# Fonte.net
KiCad netlist of a schematic drawn in Altium Designer
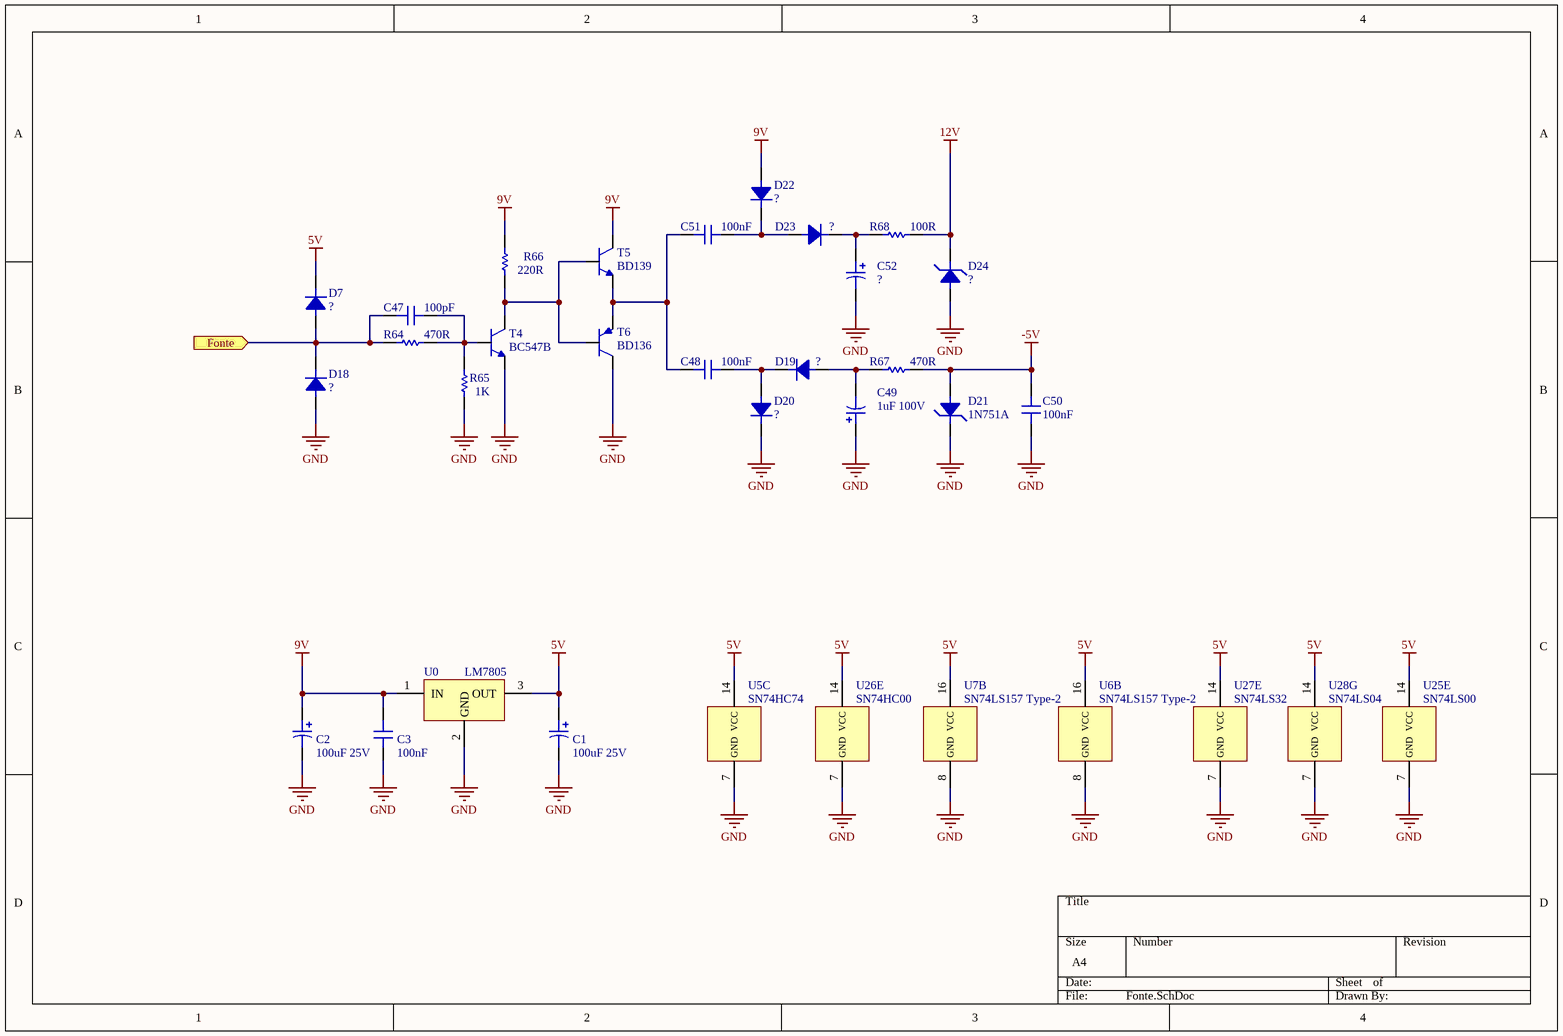
[diagram p0: Fonte.SchDoc]

(export (version "E")
  (design (tool "Eeschema 10.0.6"))
  (components
    (comp (ref "C1")
      (value "100uF 25V")
      (footprint "ECA 6.3x11.2")
      (libsource (lib "Panasonic") (part "ECA1EM101"))
    )
    (comp (ref "C2")
      (value "100uF 25V")
      (footprint "ECA 6.3x11.2")
      (libsource (lib "Panasonic") (part "ECA1EM101"))
    )
    (comp (ref "C3") (value "100nF") (footprint "DiskCapacitor") (libsource (lib "Basic") (part "Capacitor")))
    (comp (ref "C47")
      (value "100pF")
      (footprint "DiskCapacitor")
      (libsource (lib "Basic") (part "Capacitor"))
    )
    (comp (ref "C48")
      (value "100nF")
      (footprint "DiskCapacitor")
      (libsource (lib "Basic") (part "Capacitor"))
    )
    (comp (ref "C49")
      (value "1uF 100V")
      (footprint "ECA 5x11")
      (libsource (lib "Panasonic") (part "ECA2AM2R2"))
    )
    (comp (ref "C50")
      (value "100nF")
      (footprint "DiskCapacitor")
      (libsource (lib "Basic") (part "Capacitor"))
    )
    (comp (ref "C51")
      (value "100nF")
      (footprint "DiskCapacitor")
      (libsource (lib "Basic") (part "Capacitor"))
    )
    (comp (ref "C52") (value "?") (footprint "ECA 5x11") (libsource (lib "Panasonic") (part "ECA1CM100")))
    (comp (ref "D7") (value "?") (footprint "DO-15") (libsource (lib "Basic") (part "Diode")))
    (comp (ref "D18") (value "?") (footprint "DO-15") (libsource (lib "Basic") (part "Diode")))
    (comp (ref "D19") (value "?") (footprint "DO-15") (libsource (lib "Basic") (part "Diode")))
    (comp (ref "D20") (value "?") (footprint "DO-15") (libsource (lib "Basic") (part "Diode")))
    (comp (ref "D21")
      (value "1N751A")
      (footprint "DO-15")
      (description "5V1 500mW")
      (libsource (lib "Basic") (part "Diode Zener"))
    )
    (comp (ref "D22") (value "?") (footprint "DO-15") (libsource (lib "Basic") (part "Diode")))
    (comp (ref "D23") (value "?") (footprint "DO-15") (libsource (lib "Basic") (part "Diode")))
    (comp (ref "D24") (value "?") (footprint "DO-15") (libsource (lib "Basic") (part "Diode Zener")))
    (comp (ref "R64") (value "470R") (footprint "CR25") (libsource (lib "Basic") (part "Resistor")))
    (comp (ref "R65") (value "1K") (footprint "CR25") (libsource (lib "Basic") (part "Resistor")))
    (comp (ref "R66") (value "220R") (footprint "CR25") (libsource (lib "Basic") (part "Resistor")))
    (comp (ref "R67") (value "470R") (footprint "CR25") (libsource (lib "Basic") (part "Resistor")))
    (comp (ref "R68") (value "100R") (footprint "CR25") (libsource (lib "Basic") (part "Resistor")))
    (comp (ref "T4")
      (value "BC547B")
      (footprint "TO-92")
      (description "NPN Epitaxial Silicon Transistor")
      (libsource (lib "Basic") (part "BC546_47_48_49_50"))
    )
    (comp (ref "T5")
      (value "BD139")
      (footprint "TO-126")
      (description "NPN Epitaxial Silicon Transistor")
      (libsource (lib "Basic") (part "BD135_37_39"))
    )
    (comp (ref "T6")
      (value "BD136")
      (footprint "TO-126")
      (description "PNP Epitaxial Silicon Transistor")
      (libsource (lib "Basic") (part "BD136_38_40"))
    )
    (comp (ref "U0")
      (value "LM7805")
      (footprint "TO-220")
      (description "LM7805 - Positive Voltage Regulator")
      (libsource (lib "ST Microelectronics") (part "LM7805"))
    )
    (comp (ref "U5")
      (value "SN74HC74")
      (footprint "TSSOP14")
      (description "Dual D-Type Positive-Edge-Triggered Flip-Flops With Clear and Preset")
      (libsource (lib "Texas Instruments") (part "SN74HC74"))
    )
    (comp (ref "U6")
      (value "SN74LS157 Type-2")
      (footprint "TSSOP16")
      (description "Quadruple 2-Line To 1-Line Data Selectors/Mutiplexers")
      (libsource (lib "Texas Instruments") (part "SN74HC157 Type-2"))
    )
    (comp (ref "U7")
      (value "SN74LS157 Type-2")
      (footprint "TSSOP16")
      (description "Quadruple 2-Line To 1-Line Data Selectors/Mutiplexers")
      (libsource (lib "Texas Instruments") (part "SN74HC157 Type-2"))
    )
    (comp (ref "U25")
      (value "SN74LS00")
      (footprint "TSSOP14")
      (description "Quadruple 2-Input Positive-NAND Gates")
      (libsource (lib "Texas Instruments") (part "SN74HC00"))
    )
    (comp (ref "U26")
      (value "SN74HC00")
      (footprint "TSSOP14")
      (description "Quadruple 2-Input Positive-NAND Gates")
      (libsource (lib "Texas Instruments") (part "SN74HC00"))
    )
    (comp (ref "U27")
      (value "SN74LS32")
      (footprint "TSSOP14")
      (description "Quadruple 2-Input Positive-OR Gates")
      (libsource (lib "Texas Instruments") (part "SN74HC32"))
    )
    (comp (ref "U28")
      (value "SN74LS04")
      (footprint "CDIP14")
      (description "Hex Inverters")
      (libsource (lib "Texas Instruments") (part "SN74HC04"))
    )
  )
  (nets
    (net (code "1") (name "-5V") (class "Default")
      (node (ref "C50") (pin "1") (pinfunction "1_1") (pintype "passive"))
      (node (ref "D21") (pin "2") (pinfunction "2_2") (pintype "passive"))
      (node (ref "R67") (pin "1") (pinfunction "1_1") (pintype "passive"))
    )
    (net (code "2") (name "/Fonte") (class "Default")
      (node (ref "C47") (pin "2") (pinfunction "2_2") (pintype "passive"))
      (node (ref "D18") (pin "1") (pinfunction "1_1") (pintype "passive"))
      (node (ref "D7") (pin "2") (pinfunction "2_2") (pintype "passive"))
      (node (ref "R64") (pin "2") (pinfunction "2_2") (pintype "passive"))
    )
    (net (code "3") (name "5V") (class "Default")
      (node (ref "C1") (pin "1") (pinfunction "1_1") (pintype "passive"))
      (node (ref "D7") (pin "1") (pinfunction "1_1") (pintype "passive"))
      (node (ref "U0") (pin "3") (pinfunction "OUT_3") (pintype "power_in"))
      (node (ref "U25") (pin "14") (pinfunction "VCC_14") (pintype "power_in"))
      (node (ref "U26") (pin "14") (pinfunction "VCC_14") (pintype "power_in"))
      (node (ref "U27") (pin "14") (pinfunction "VCC_14") (pintype "power_in"))
      (node (ref "U28") (pin "14") (pinfunction "VCC_14") (pintype "power_in"))
      (node (ref "U5") (pin "14") (pinfunction "VCC_14") (pintype "power_in"))
      (node (ref "U6") (pin "16") (pinfunction "VCC_16") (pintype "power_in"))
      (node (ref "U7") (pin "16") (pinfunction "VCC_16") (pintype "power_in"))
    )
    (net (code "4") (name "9V") (class "Default")
      (node (ref "C2") (pin "1") (pinfunction "1_1") (pintype "passive"))
      (node (ref "C3") (pin "2") (pinfunction "2_2") (pintype "passive"))
      (node (ref "D22") (pin "2") (pinfunction "2_2") (pintype "passive"))
      (node (ref "R66") (pin "2") (pinfunction "2_2") (pintype "passive"))
      (node (ref "T5") (pin "2") (pinfunction "2_2") (pintype "passive"))
      (node (ref "U0") (pin "1") (pinfunction "IN_1") (pintype "power_in"))
    )
    (net (code "5") (name "12V") (class "Default")
      (node (ref "D24") (pin "1") (pinfunction "1_1") (pintype "passive"))
      (node (ref "R68") (pin "1") (pinfunction "1_1") (pintype "passive"))
    )
    (net (code "6") (name "GND") (class "Default")
      (node (ref "C1") (pin "2") (pinfunction "2_2") (pintype "passive"))
      (node (ref "C2") (pin "2") (pinfunction "2_2") (pintype "passive"))
      (node (ref "C3") (pin "1") (pinfunction "1_1") (pintype "passive"))
      (node (ref "C49") (pin "1") (pinfunction "1_1") (pintype "passive"))
      (node (ref "C50") (pin "2") (pinfunction "2_2") (pintype "passive"))
      (node (ref "C52") (pin "2") (pinfunction "2_2") (pintype "passive"))
      (node (ref "D18") (pin "2") (pinfunction "2_2") (pintype "passive"))
      (node (ref "D20") (pin "1") (pinfunction "1_1") (pintype "passive"))
      (node (ref "D21") (pin "1") (pinfunction "1_1") (pintype "passive"))
      (node (ref "D24") (pin "2") (pinfunction "2_2") (pintype "passive"))
      (node (ref "R65") (pin "1") (pinfunction "1_1") (pintype "passive"))
      (node (ref "T4") (pin "1") (pinfunction "1_1") (pintype "passive"))
      (node (ref "T6") (pin "2") (pinfunction "2_2") (pintype "passive"))
      (node (ref "U0") (pin "2") (pinfunction "GND_2") (pintype "power_in"))
      (node (ref "U25") (pin "7") (pinfunction "GND_7") (pintype "power_in"))
      (node (ref "U26") (pin "7") (pinfunction "GND_7") (pintype "power_in"))
      (node (ref "U27") (pin "7") (pinfunction "GND_7") (pintype "power_in"))
      (node (ref "U28") (pin "7") (pinfunction "GND_7") (pintype "power_in"))
      (node (ref "U5") (pin "7") (pinfunction "GND_7") (pintype "power_in"))
      (node (ref "U6") (pin "8") (pinfunction "GND_8") (pintype "power_in"))
      (node (ref "U7") (pin "8") (pinfunction "GND_8") (pintype "power_in"))
    )
    (net (code "7") (name "Net-(C47-Pad1)") (class "Default")
      (node (ref "C47") (pin "1") (pinfunction "1_1") (pintype "passive"))
      (node (ref "R64") (pin "1") (pinfunction "1_1") (pintype "passive"))
      (node (ref "R65") (pin "2") (pinfunction "2_2") (pintype "passive"))
      (node (ref "T4") (pin "2") (pinfunction "2_2") (pintype "passive"))
    )
    (net (code "8") (name "Net-(C48-Pad1)") (class "Default")
      (node (ref "C48") (pin "1") (pinfunction "1_1") (pintype "passive"))
      (node (ref "D19") (pin "1") (pinfunction "1_1") (pintype "passive"))
      (node (ref "D20") (pin "2") (pinfunction "2_2") (pintype "passive"))
    )
    (net (code "9") (name "Net-(C48-Pad2)") (class "Default")
      (node (ref "C48") (pin "2") (pinfunction "2_2") (pintype "passive"))
      (node (ref "C51") (pin "2") (pinfunction "2_2") (pintype "passive"))
      (node (ref "T5") (pin "1") (pinfunction "1_1") (pintype "passive"))
      (node (ref "T6") (pin "1") (pinfunction "1_1") (pintype "passive"))
    )
    (net (code "10") (name "Net-(C49-Pad2)") (class "Default")
      (node (ref "C49") (pin "2") (pinfunction "2_2") (pintype "passive"))
      (node (ref "D19") (pin "2") (pinfunction "2_2") (pintype "passive"))
      (node (ref "R67") (pin "2") (pinfunction "2_2") (pintype "passive"))
    )
    (net (code "11") (name "Net-(C51-Pad1)") (class "Default")
      (node (ref "C51") (pin "1") (pinfunction "1_1") (pintype "passive"))
      (node (ref "D22") (pin "1") (pinfunction "1_1") (pintype "passive"))
      (node (ref "D23") (pin "2") (pinfunction "2_2") (pintype "passive"))
    )
    (net (code "12") (name "Net-(C52-Pad1)") (class "Default")
      (node (ref "C52") (pin "1") (pinfunction "1_1") (pintype "passive"))
      (node (ref "D23") (pin "1") (pinfunction "1_1") (pintype "passive"))
      (node (ref "R68") (pin "2") (pinfunction "2_2") (pintype "passive"))
    )
    (net (code "13") (name "Net-(R66-Pad1)") (class "Default")
      (node (ref "R66") (pin "1") (pinfunction "1_1") (pintype "passive"))
      (node (ref "T4") (pin "3") (pinfunction "3_3") (pintype "passive"))
      (node (ref "T5") (pin "3") (pinfunction "3_3") (pintype "passive"))
      (node (ref "T6") (pin "3") (pinfunction "3_3") (pintype "passive"))
    )
  )
)
